# FootSW.net
KiCad netlist of a schematic drawn in Altium Designer
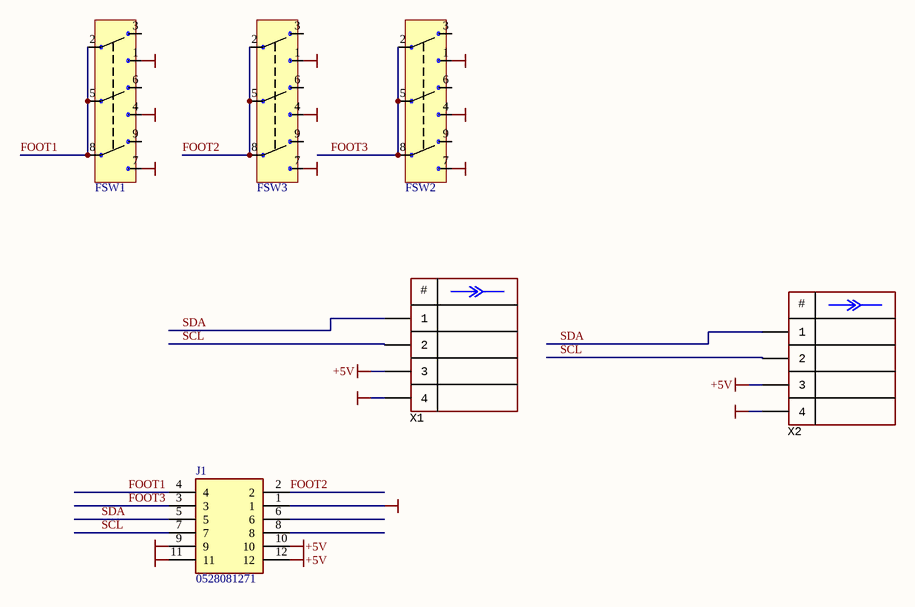
[diagram p0: FootSW.SchDoc]

(export (version "E")
  (design (tool "Eeschema 10.0.6"))
  (components
    (comp (ref "FSW1")
      (value "FootSwitch")
      (footprint "ProtoStack_H750VBT:FOOTSW")
      (libsource (lib "ProtoStack_H750VBT") (part "FootSwitch"))
    )
    (comp (ref "FSW2")
      (value "FootSwitch")
      (footprint "ProtoStack_H750VBT:FOOTSW")
      (libsource (lib "ProtoStack_H750VBT") (part "FootSwitch"))
    )
    (comp (ref "FSW3")
      (value "FootSwitch")
      (footprint "ProtoStack_H750VBT:FOOTSW")
      (libsource (lib "ProtoStack_H750VBT") (part "FootSwitch"))
    )
    (comp (ref "J1")
      (value "0528081271")
      (footprint "ProtoStack_H750VBT:AFA11-S12GLA-00")
      (description "Connector")
      (libsource (lib "ProtoStack_H750VBT") (part "0528081271"))
    )
    (comp (ref "X1")
      (value "~")
      (footprint "CON: PBS-4")
      (fields
        (field (name "MANUFACTURER") "Connfly")
        (field (name "VALUEMANUFACTURERPARTNUMBER") "Connector, 4pin, 2.54mm, 500VAC, 3A")
        (field (name "PARTNUMBER") "PBS-4")
      )
      (libsource (lib "connector") (part "PBS-4"))
    )
    (comp (ref "X2")
      (value "~")
      (footprint "CON: PBS-4")
      (fields
        (field (name "MANUFACTURER") "Connfly")
        (field (name "VALUEMANUFACTURERPARTNUMBER") "Connector, 4pin, 2.54mm, 500VAC, 3A")
        (field (name "PARTNUMBER") "PBS-4")
      )
      (libsource (lib "connector") (part "PBS-4"))
    )
  )
  (nets
    (net (code "1") (name "+5V") (class "Default")
      (node (ref "J1") (pin "10") (pinfunction "10_10") (pintype "passive"))
      (node (ref "J1") (pin "12") (pinfunction "12_12") (pintype "passive"))
      (node (ref "X1") (pin "3") (pinfunction "3_3") (pintype "power_in"))
      (node (ref "X2") (pin "3") (pinfunction "3_3") (pintype "power_in"))
    )
    (net (code "2") (name "/FOOT1") (class "Default")
      (node (ref "FSW1") (pin "2") (pinfunction "2_2") (pintype "passive"))
      (node (ref "FSW1") (pin "5") (pinfunction "5_5") (pintype "passive"))
      (node (ref "FSW1") (pin "8") (pinfunction "8_8") (pintype "passive"))
      (node (ref "J1") (pin "4") (pinfunction "4_4") (pintype "passive"))
    )
    (net (code "3") (name "/FOOT2") (class "Default")
      (node (ref "FSW3") (pin "2") (pinfunction "2_2") (pintype "passive"))
      (node (ref "FSW3") (pin "5") (pinfunction "5_5") (pintype "passive"))
      (node (ref "FSW3") (pin "8") (pinfunction "8_8") (pintype "passive"))
      (node (ref "J1") (pin "2") (pinfunction "2_2") (pintype "passive"))
    )
    (net (code "4") (name "/FOOT3") (class "Default")
      (node (ref "FSW2") (pin "2") (pinfunction "2_2") (pintype "passive"))
      (node (ref "FSW2") (pin "5") (pinfunction "5_5") (pintype "passive"))
      (node (ref "FSW2") (pin "8") (pinfunction "8_8") (pintype "passive"))
      (node (ref "J1") (pin "3") (pinfunction "3_3") (pintype "passive"))
    )
    (net (code "5") (name "/SC~{L}") (class "Default")
      (node (ref "J1") (pin "7") (pinfunction "7_7") (pintype "passive"))
      (node (ref "X1") (pin "2") (pinfunction "2_2") (pintype "passive"))
      (node (ref "X2") (pin "2") (pinfunction "2_2") (pintype "passive"))
    )
    (net (code "6") (name "/SDA") (class "Default")
      (node (ref "J1") (pin "5") (pinfunction "5_5") (pintype "passive"))
      (node (ref "X1") (pin "1") (pinfunction "1_1") (pintype "passive"))
      (node (ref "X2") (pin "1") (pinfunction "1_1") (pintype "passive"))
    )
    (net (code "7") (name "GND") (class "Default")
      (node (ref "FSW1") (pin "1") (pinfunction "1_1") (pintype "passive"))
      (node (ref "FSW1") (pin "4") (pinfunction "4_4") (pintype "passive"))
      (node (ref "FSW1") (pin "7") (pinfunction "7_7") (pintype "passive"))
      (node (ref "FSW2") (pin "1") (pinfunction "1_1") (pintype "passive"))
      (node (ref "FSW2") (pin "4") (pinfunction "4_4") (pintype "passive"))
      (node (ref "FSW2") (pin "7") (pinfunction "7_7") (pintype "passive"))
      (node (ref "FSW3") (pin "1") (pinfunction "1_1") (pintype "passive"))
      (node (ref "FSW3") (pin "4") (pinfunction "4_4") (pintype "passive"))
      (node (ref "FSW3") (pin "7") (pinfunction "7_7") (pintype "passive"))
      (node (ref "J1") (pin "1") (pinfunction "1_1") (pintype "passive"))
      (node (ref "J1") (pin "11") (pinfunction "11_11") (pintype "passive"))
      (node (ref "J1") (pin "9") (pinfunction "9_9") (pintype "passive"))
      (node (ref "X1") (pin "4") (pinfunction "4_4") (pintype "power_in"))
      (node (ref "X2") (pin "4") (pinfunction "4_4") (pintype "power_in"))
    )
    (net (code "8") (name "unconnected-(FSW1-Pad3)") (class "Default")
      (node (ref "FSW1") (pin "3") (pinfunction "3_3") (pintype "passive"))
    )
    (net (code "9") (name "unconnected-(FSW1-Pad6)") (class "Default")
      (node (ref "FSW1") (pin "6") (pinfunction "6_6") (pintype "passive"))
    )
    (net (code "10") (name "unconnected-(FSW1-Pad9)") (class "Default")
      (node (ref "FSW1") (pin "9") (pinfunction "9_9") (pintype "passive"))
    )
    (net (code "11") (name "unconnected-(FSW2-Pad3)") (class "Default")
      (node (ref "FSW2") (pin "3") (pinfunction "3_3") (pintype "passive"))
    )
    (net (code "12") (name "unconnected-(FSW2-Pad6)") (class "Default")
      (node (ref "FSW2") (pin "6") (pinfunction "6_6") (pintype "passive"))
    )
    (net (code "13") (name "unconnected-(FSW2-Pad9)") (class "Default")
      (node (ref "FSW2") (pin "9") (pinfunction "9_9") (pintype "passive"))
    )
    (net (code "14") (name "unconnected-(FSW3-Pad3)") (class "Default")
      (node (ref "FSW3") (pin "3") (pinfunction "3_3") (pintype "passive"))
    )
    (net (code "15") (name "unconnected-(FSW3-Pad6)") (class "Default")
      (node (ref "FSW3") (pin "6") (pinfunction "6_6") (pintype "passive"))
    )
    (net (code "16") (name "unconnected-(FSW3-Pad9)") (class "Default")
      (node (ref "FSW3") (pin "9") (pinfunction "9_9") (pintype "passive"))
    )
    (net (code "17") (name "unconnected-(J1-Pad6)") (class "Default")
      (node (ref "J1") (pin "6") (pinfunction "6_6") (pintype "passive"))
    )
    (net (code "18") (name "unconnected-(J1-Pad8)") (class "Default")
      (node (ref "J1") (pin "8") (pinfunction "8_8") (pintype "passive"))
    )
  )
)
